# Sheet1.net
KiCad netlist of a schematic drawn in Altium Designer
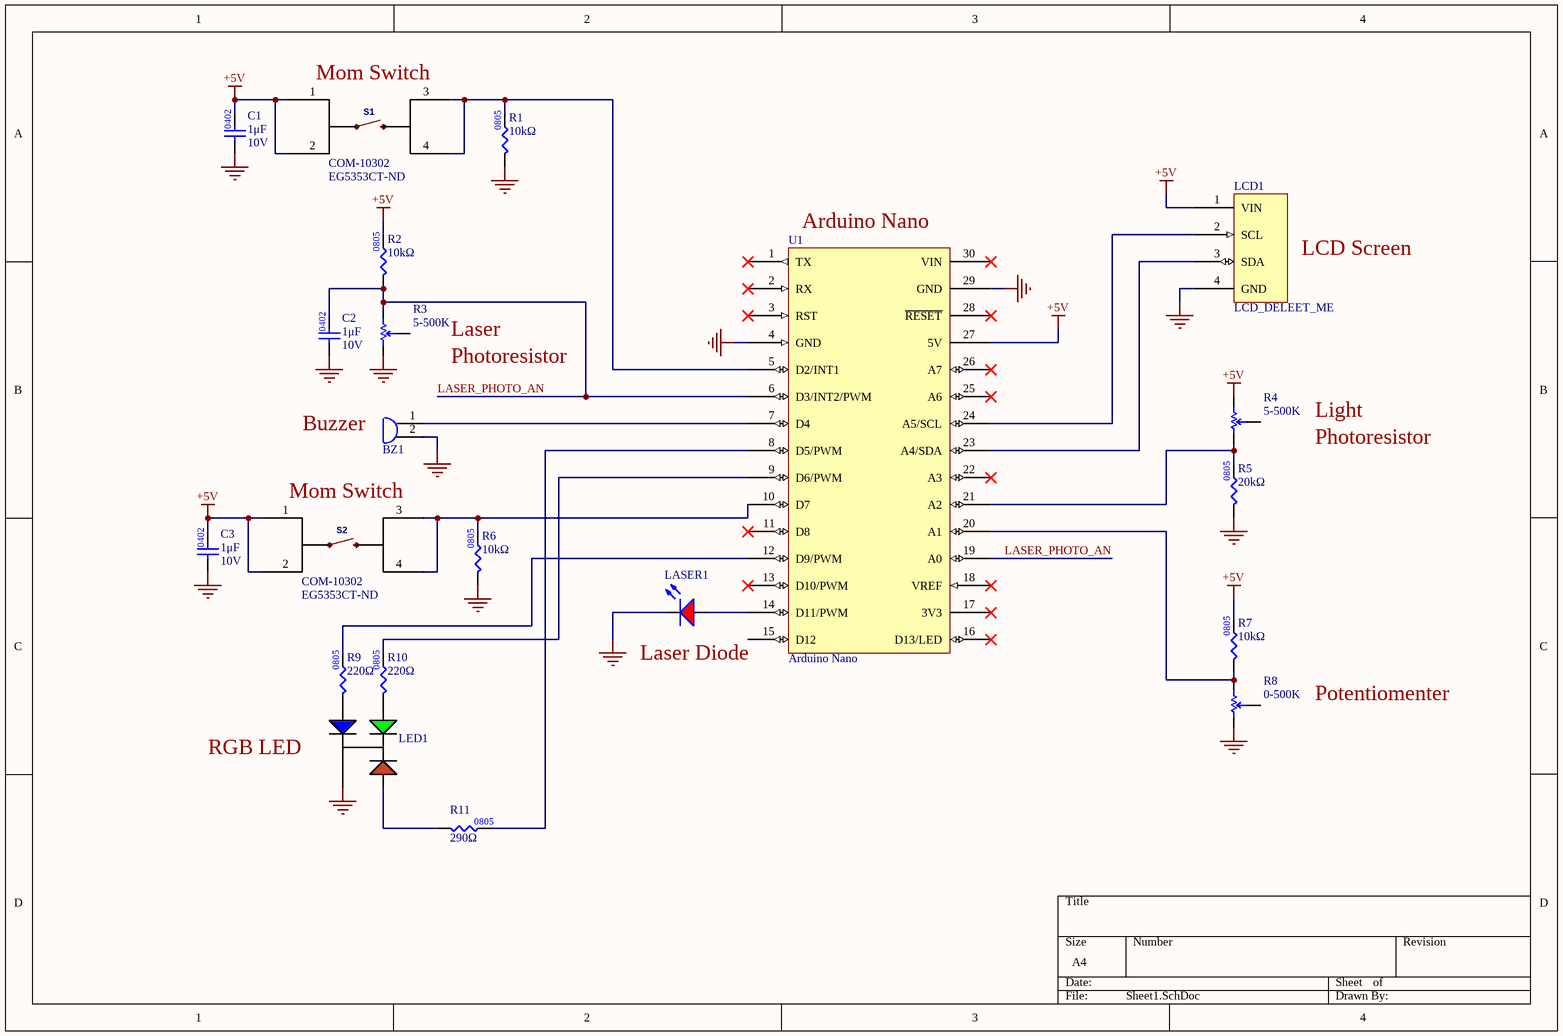
[diagram p0: Sheet1.SchDoc]

(export (version "E")
  (design (tool "Eeschema 10.0.6"))
  (components
    (comp (ref "BZ1")
      (value "CMI-1275C-050")
      (footprint "SamacSys:CMI1275C050")
      (description "Buzzer")
      (fields (field (name "MOUSER PART NUMBER") "490-CMI-1275C-050"))
      (libsource (lib "UWRT_Schematic_Library_2020") (part "CMI-1275C-050"))
    )
    (comp (ref "C1")
      (value "CAP_1UF_10V_0402_X5R")
      (footprint "CAP0402")
      (description "CAP CER 1UF 10V X5R 0402")
      (fields
        (field (name "MANUFACTURER") "Kyocera AVX")
        (field (name "MANUFACTURER PART NUMBER") "0402ZD105MAT2A")
        (field (name "CAPACITANCE") "1μF")
        (field (name "RATED DC VOLTAGE (URDC)") "10V")
      )
      (libsource (lib "UWRT_Schematic_Library_2020") (part "CAP_1UF_10V_0402_X5R"))
    )
    (comp (ref "C2")
      (value "CAP_1UF_10V_0402_X5R")
      (footprint "CAP0402")
      (description "CAP CER 1UF 10V X5R 0402")
      (fields
        (field (name "MANUFACTURER") "Kyocera AVX")
        (field (name "MANUFACTURER PART NUMBER") "0402ZD105MAT2A")
        (field (name "CAPACITANCE") "1μF")
        (field (name "RATED DC VOLTAGE (URDC)") "10V")
      )
      (libsource (lib "UWRT_Schematic_Library_2020") (part "CAP_1UF_10V_0402_X5R"))
    )
    (comp (ref "C3")
      (value "CAP_1UF_10V_0402_X5R")
      (footprint "CAP0402")
      (description "CAP CER 1UF 10V X5R 0402")
      (fields
        (field (name "MANUFACTURER") "Kyocera AVX")
        (field (name "MANUFACTURER PART NUMBER") "0402ZD105MAT2A")
        (field (name "CAPACITANCE") "1μF")
        (field (name "RATED DC VOLTAGE (URDC)") "10V")
      )
      (libsource (lib "UWRT_Schematic_Library_2020") (part "CAP_1UF_10V_0402_X5R"))
    )
    (comp (ref "LASER1")
      (value "LED_RED")
      (footprint "LED_0805_RED")
      (description "LED RED DIFFUSED 0805 SMD")
      (libsource (lib "UWRT_Schematic_Library_2020") (part "LED_RED"))
    )
    (comp (ref "LCD1")
      (value "LCD_DELEET_ME")
      (libsource (lib "UWRT_Schematic_Library_2020") (part "LCD_DELEET_ME"))
    )
    (comp (ref "LED1")
      (value "LED_RGB_CA")
      (footprint "LED_RGB")
      (description "LED RGB DIFFUSED 4PLCC SMD")
      (libsource (lib "UWRT_Schematic_Library_2020") (part "LED_RGB_CA"))
    )
    (comp (ref "R1")
      (value "10kΩ")
      (footprint "RES0805")
      (description "RES 10K OHM 5% 1/8W 0805")
      (fields (field (name "LCSC PART #") "C17414") (field (name "Comment") "RES_10kΩ_0805_5%"))
      (libsource (lib "UWRT_Schematic_Library_2020") (part "RES_10kΩ_0805_5%"))
    )
    (comp (ref "R2")
      (value "10kΩ")
      (footprint "RES0805")
      (description "RES 10K OHM 5% 1/8W 0805")
      (fields (field (name "LCSC PART #") "C17414") (field (name "Comment") "RES_10kΩ_0805_5%"))
      (libsource (lib "UWRT_Schematic_Library_2020") (part "RES_10kΩ_0805_5%"))
    )
    (comp (ref "R3")
      (value "5-500K")
      (footprint "3362P-1-502LF")
      (description "TRIMMER 5K OHM 0.5W PC PIN TOP")
      (fields (field (name "Comment") "POT_5K"))
      (libsource (lib "UWRT_Schematic_Library_2020") (part "POT_5K"))
    )
    (comp (ref "R4")
      (value "5-500K")
      (footprint "3362P-1-502LF")
      (description "TRIMMER 5K OHM 0.5W PC PIN TOP")
      (fields (field (name "Comment") "POT_5K"))
      (libsource (lib "UWRT_Schematic_Library_2020") (part "POT_5K"))
    )
    (comp (ref "R5")
      (value "20kΩ")
      (footprint "RES0805")
      (description "RES 20K OHM 1% 1/8W 0805")
      (fields (field (name "LCSC PART #") "C4328") (field (name "Comment") "RES_20kΩ_0805_1%"))
      (libsource (lib "UWRT_Schematic_Library_2020") (part "RES_20kΩ_0805_1%"))
    )
    (comp (ref "R6")
      (value "10kΩ")
      (footprint "RES0805")
      (description "RES 10K OHM 5% 1/8W 0805")
      (fields (field (name "LCSC PART #") "C17414") (field (name "Comment") "RES_10kΩ_0805_5%"))
      (libsource (lib "UWRT_Schematic_Library_2020") (part "RES_10kΩ_0805_5%"))
    )
    (comp (ref "R7")
      (value "10kΩ")
      (footprint "RES0805")
      (description "RES 10K OHM 5% 1/8W 0805")
      (fields (field (name "LCSC PART #") "C17414") (field (name "Comment") "RES_10kΩ_0805_5%"))
      (libsource (lib "UWRT_Schematic_Library_2020") (part "RES_10kΩ_0805_5%"))
    )
    (comp (ref "R8")
      (value "0-500K")
      (footprint "3362P-1-502LF")
      (description "TRIMMER 5K OHM 0.5W PC PIN TOP")
      (fields (field (name "Comment") "POT_5K"))
      (libsource (lib "UWRT_Schematic_Library_2020") (part "POT_5K"))
    )
    (comp (ref "R9")
      (value "220Ω")
      (footprint "RES0805")
      (description "RES 220 OHM 5% 1/2W 0805")
      (fields (field (name "LCSC PART #") "C17557") (field (name "Comment") "RES_220Ω_0805_5%"))
      (libsource (lib "UWRT_Schematic_Library_2020") (part "RES_220Ω_0805_5%"))
    )
    (comp (ref "R10")
      (value "220Ω")
      (footprint "RES0805")
      (description "RES 220 OHM 5% 1/2W 0805")
      (fields (field (name "LCSC PART #") "C17557") (field (name "Comment") "RES_220Ω_0805_5%"))
      (libsource (lib "UWRT_Schematic_Library_2020") (part "RES_220Ω_0805_5%"))
    )
    (comp (ref "R11")
      (value "290Ω")
      (footprint "RES0805")
      (description "RES 220 OHM 5% 1/2W 0805")
      (fields (field (name "LCSC PART #") "C17557") (field (name "Comment") "RES_220Ω_0805_5%"))
      (libsource (lib "UWRT_Schematic_Library_2020") (part "RES_220Ω_0805_5%"))
    )
    (comp (ref "S1")
      (value "SW_MOMENTARY_PUSHBUTTON")
      (footprint "TACTILE_SWITCH_PTH_12MM")
      (description "TL3305A Series SPST 12 V 4.5 x 4.5 mm 260 gf Top Actuated SMT Tactile Switch")
      (fields
        (field (name "MANUFACTURER") "E-Switch")
        (field (name "MANUFACTURER PART NUMBER") "TL3305AF260QG")
        (field (name "MANUFACTURER PART NUMBER 1") "COM-10302")
        (field (name "SUPPLIER PART NUMBER 2") "EG5353CT-ND")
      )
      (libsource (lib "UWRT_Schematic_Library_2020") (part "SW_MOMENTARY_PUSHBUTTON"))
    )
    (comp (ref "S2")
      (value "SW_MOMENTARY_PUSHBUTTON")
      (footprint "TACTILE_SWITCH_PTH_12MM")
      (description "TL3305A Series SPST 12 V 4.5 x 4.5 mm 260 gf Top Actuated SMT Tactile Switch")
      (fields
        (field (name "MANUFACTURER") "E-Switch")
        (field (name "MANUFACTURER PART NUMBER") "TL3305AF260QG")
        (field (name "MANUFACTURER PART NUMBER 1") "COM-10302")
        (field (name "SUPPLIER PART NUMBER 2") "EG5353CT-ND")
      )
      (libsource (lib "UWRT_Schematic_Library_2020") (part "SW_MOMENTARY_PUSHBUTTON"))
    )
    (comp (ref "U1")
      (value "Arduino Nano")
      (libsource (lib "UWRT_Schematic_Library_2020") (part "DELETE_ME"))
    )
  )
  (nets
    (net (code "1") (name "+5V") (class "Default")
      (node (ref "C1") (pin "2") (pinfunction "2_2") (pintype "passive"))
      (node (ref "C3") (pin "2") (pinfunction "2_2") (pintype "passive"))
      (node (ref "LCD1") (pin "1") (pinfunction "VIN_1") (pintype "power_in"))
      (node (ref "R2") (pin "2") (pinfunction "2_2") (pintype "passive"))
      (node (ref "R4") (pin "2") (pinfunction "2_2") (pintype "passive"))
      (node (ref "R7") (pin "2") (pinfunction "2_2") (pintype "passive"))
      (node (ref "S1") (pin "1") (pinfunction "1_1") (pintype "passive"))
      (node (ref "S1") (pin "2") (pinfunction "2_2") (pintype "passive"))
      (node (ref "S2") (pin "1") (pinfunction "1_1") (pintype "passive"))
      (node (ref "S2") (pin "2") (pinfunction "2_2") (pintype "passive"))
      (node (ref "U1") (pin "27") (pinfunction "5V_27") (pintype "power_in"))
    )
    (net (code "2") (name "/LASER_PHOTO_AN") (class "Default")
      (node (ref "C2") (pin "2") (pinfunction "2_2") (pintype "passive"))
      (node (ref "R2") (pin "1") (pinfunction "1_1") (pintype "passive"))
      (node (ref "R3") (pin "2") (pinfunction "2_2") (pintype "passive"))
      (node (ref "U1") (pin "19") (pinfunction "A0_19") (pintype "bidirectional"))
      (node (ref "U1") (pin "6") (pinfunction "D3/INT2/PWM_6") (pintype "bidirectional"))
    )
    (net (code "3") (name "GND") (class "Default")
      (node (ref "BZ1") (pin "2") (pinfunction "2_2") (pintype "passive"))
      (node (ref "C1") (pin "1") (pinfunction "1_1") (pintype "passive"))
      (node (ref "C2") (pin "1") (pinfunction "1_1") (pintype "passive"))
      (node (ref "C3") (pin "1") (pinfunction "1_1") (pintype "passive"))
      (node (ref "LASER1") (pin "2") (pinfunction "K_2") (pintype "passive"))
      (node (ref "LCD1") (pin "4") (pinfunction "GND_4") (pintype "power_in"))
      (node (ref "LED1") (pin "4") (pinfunction "COMMON_ANODE_4") (pintype "passive"))
      (node (ref "R1") (pin "1") (pinfunction "1_1") (pintype "passive"))
      (node (ref "R3") (pin "1") (pinfunction "1_1") (pintype "passive"))
      (node (ref "R5") (pin "1") (pinfunction "1_1") (pintype "passive"))
      (node (ref "R6") (pin "1") (pinfunction "1_1") (pintype "passive"))
      (node (ref "R8") (pin "1") (pinfunction "1_1") (pintype "passive"))
      (node (ref "U1") (pin "29") (pinfunction "GND_29") (pintype "power_in"))
      (node (ref "U1") (pin "4") (pinfunction "GND_4") (pintype "input"))
    )
    (net (code "4") (name "Net-(LASER1-A)") (class "Default")
      (node (ref "LASER1") (pin "1") (pinfunction "A_1") (pintype "passive"))
      (node (ref "U1") (pin "14") (pinfunction "D11/PWM_14") (pintype "bidirectional"))
    )
    (net (code "5") (name "Net-(LCD1-SCL)") (class "Default")
      (node (ref "LCD1") (pin "2") (pinfunction "SCL_2") (pintype "input"))
      (node (ref "U1") (pin "24") (pinfunction "A5/SCL_24") (pintype "bidirectional"))
    )
    (net (code "6") (name "Net-(LCD1-SDA)") (class "Default")
      (node (ref "LCD1") (pin "3") (pinfunction "SDA_3") (pintype "bidirectional"))
      (node (ref "U1") (pin "23") (pinfunction "A4/SDA_23") (pintype "bidirectional"))
    )
    (net (code "7") (name "Net-(LED1-CATHODE_(BLUE))") (class "Default")
      (node (ref "LED1") (pin "3") (pinfunction "CATHODE_(BLUE)_3") (pintype "passive"))
      (node (ref "R9") (pin "1") (pinfunction "1_1") (pintype "passive"))
    )
    (net (code "8") (name "Net-(LED1-CATHODE_(GREEN))") (class "Default")
      (node (ref "LED1") (pin "2") (pinfunction "CATHODE_(GREEN)_2") (pintype "passive"))
      (node (ref "R10") (pin "1") (pinfunction "1_1") (pintype "passive"))
    )
    (net (code "9") (name "Net-(LED1-CATHODE_(RED))") (class "Default")
      (node (ref "LED1") (pin "1") (pinfunction "CATHODE_(RED)_1") (pintype "passive"))
      (node (ref "R11") (pin "1") (pinfunction "1_1") (pintype "passive"))
    )
    (net (code "10") (name "Net-(U1-A1)") (class "Default")
      (node (ref "R7") (pin "1") (pinfunction "1_1") (pintype "passive"))
      (node (ref "R8") (pin "2") (pinfunction "2_2") (pintype "passive"))
      (node (ref "U1") (pin "20") (pinfunction "A1_20") (pintype "bidirectional"))
    )
    (net (code "11") (name "Net-(U1-A2)") (class "Default")
      (node (ref "R4") (pin "1") (pinfunction "1_1") (pintype "passive"))
      (node (ref "R5") (pin "2") (pinfunction "2_2") (pintype "passive"))
      (node (ref "U1") (pin "21") (pinfunction "A2_21") (pintype "bidirectional"))
    )
    (net (code "12") (name "Net-(U1-D2{slash}INT1)") (class "Default")
      (node (ref "R1") (pin "2") (pinfunction "2_2") (pintype "passive"))
      (node (ref "S1") (pin "3") (pinfunction "3_3") (pintype "passive"))
      (node (ref "S1") (pin "4") (pinfunction "4_4") (pintype "passive"))
      (node (ref "U1") (pin "5") (pinfunction "D2/INT1_5") (pintype "bidirectional"))
    )
    (net (code "13") (name "Net-(U1-D4)") (class "Default")
      (node (ref "BZ1") (pin "1") (pinfunction "1_1") (pintype "passive"))
      (node (ref "U1") (pin "7") (pinfunction "D4_7") (pintype "bidirectional"))
    )
    (net (code "14") (name "Net-(U1-D5{slash}PWM)") (class "Default")
      (node (ref "R11") (pin "2") (pinfunction "2_2") (pintype "passive"))
      (node (ref "U1") (pin "8") (pinfunction "D5/PWM_8") (pintype "bidirectional"))
    )
    (net (code "15") (name "Net-(U1-D6{slash}PWM)") (class "Default")
      (node (ref "R10") (pin "2") (pinfunction "2_2") (pintype "passive"))
      (node (ref "U1") (pin "9") (pinfunction "D6/PWM_9") (pintype "bidirectional"))
    )
    (net (code "16") (name "Net-(U1-D7)") (class "Default")
      (node (ref "R6") (pin "2") (pinfunction "2_2") (pintype "passive"))
      (node (ref "S2") (pin "3") (pinfunction "3_3") (pintype "passive"))
      (node (ref "S2") (pin "4") (pinfunction "4_4") (pintype "passive"))
      (node (ref "U1") (pin "10") (pinfunction "D7_10") (pintype "bidirectional"))
    )
    (net (code "17") (name "Net-(U1-D9{slash}PWM)") (class "Default")
      (node (ref "R9") (pin "2") (pinfunction "2_2") (pintype "passive"))
      (node (ref "U1") (pin "12") (pinfunction "D9/PWM_12") (pintype "bidirectional"))
    )
    (net (code "18") (name "unconnected-(R3-Pad3)") (class "Default")
      (node (ref "R3") (pin "3") (pinfunction "3_3") (pintype "passive"))
    )
    (net (code "19") (name "unconnected-(R4-Pad3)") (class "Default")
      (node (ref "R4") (pin "3") (pinfunction "3_3") (pintype "passive"))
    )
    (net (code "20") (name "unconnected-(R8-Pad3)") (class "Default")
      (node (ref "R8") (pin "3") (pinfunction "3_3") (pintype "passive"))
    )
    (net (code "21") (name "unconnected-(U1-3V3-Pad17)") (class "Default")
      (node (ref "U1") (pin "17") (pinfunction "3V3_17") (pintype "power_in+no_connect"))
    )
    (net (code "22") (name "unconnected-(U1-A3-Pad22)") (class "Default")
      (node (ref "U1") (pin "22") (pinfunction "A3_22") (pintype "bidirectional+no_connect"))
    )
    (net (code "23") (name "unconnected-(U1-A6-Pad25)") (class "Default")
      (node (ref "U1") (pin "25") (pinfunction "A6_25") (pintype "bidirectional+no_connect"))
    )
    (net (code "24") (name "unconnected-(U1-A7-Pad26)") (class "Default")
      (node (ref "U1") (pin "26") (pinfunction "A7_26") (pintype "bidirectional+no_connect"))
    )
    (net (code "25") (name "unconnected-(U1-D8-Pad11)") (class "Default")
      (node (ref "U1") (pin "11") (pinfunction "D8_11") (pintype "bidirectional+no_connect"))
    )
    (net (code "26") (name "unconnected-(U1-D10{slash}PWM-Pad13)") (class "Default")
      (node (ref "U1") (pin "13") (pinfunction "D10/PWM_13") (pintype "bidirectional+no_connect"))
    )
    (net (code "27") (name "unconnected-(U1-D12-Pad15)") (class "Default")
      (node (ref "U1") (pin "15") (pinfunction "D12_15") (pintype "bidirectional"))
    )
    (net (code "28") (name "unconnected-(U1-D13{slash}LED-Pad16)") (class "Default")
      (node (ref "U1") (pin "16") (pinfunction "D13/LED_16") (pintype "bidirectional+no_connect"))
    )
    (net (code "29") (name "unconnected-(U1-RST-Pad3)") (class "Default")
      (node (ref "U1") (pin "3") (pinfunction "RST_3") (pintype "input+no_connect"))
    )
    (net (code "30") (name "unconnected-(U1-RX-Pad2)") (class "Default")
      (node (ref "U1") (pin "2") (pinfunction "RX_2") (pintype "input+no_connect"))
    )
    (net (code "31") (name "unconnected-(U1-TX-Pad1)") (class "Default")
      (node (ref "U1") (pin "1") (pinfunction "TX_1") (pintype "output+no_connect"))
    )
    (net (code "32") (name "unconnected-(U1-VIN-Pad30)") (class "Default")
      (node (ref "U1") (pin "30") (pinfunction "VIN_30") (pintype "power_in+no_connect"))
    )
    (net (code "33") (name "unconnected-(U1-VREF-Pad18)") (class "Default")
      (node (ref "U1") (pin "18") (pinfunction "VREF_18") (pintype "input+no_connect"))
    )
    (net (code "34") (name "unconnected-(U1-~{RESET}-Pad28)") (class "Default")
      (node (ref "U1") (pin "28") (pinfunction "~{RESET}_28") (pintype "power_in+no_connect"))
    )
  )
)
